# Handy_sense_v_1_0_1.net
KiCad netlist of a schematic drawn in EAGLE
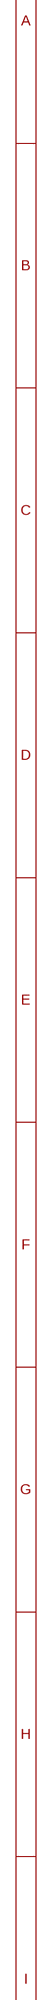
[diagram p0: schematic, sheet 1, part 1 of 2]
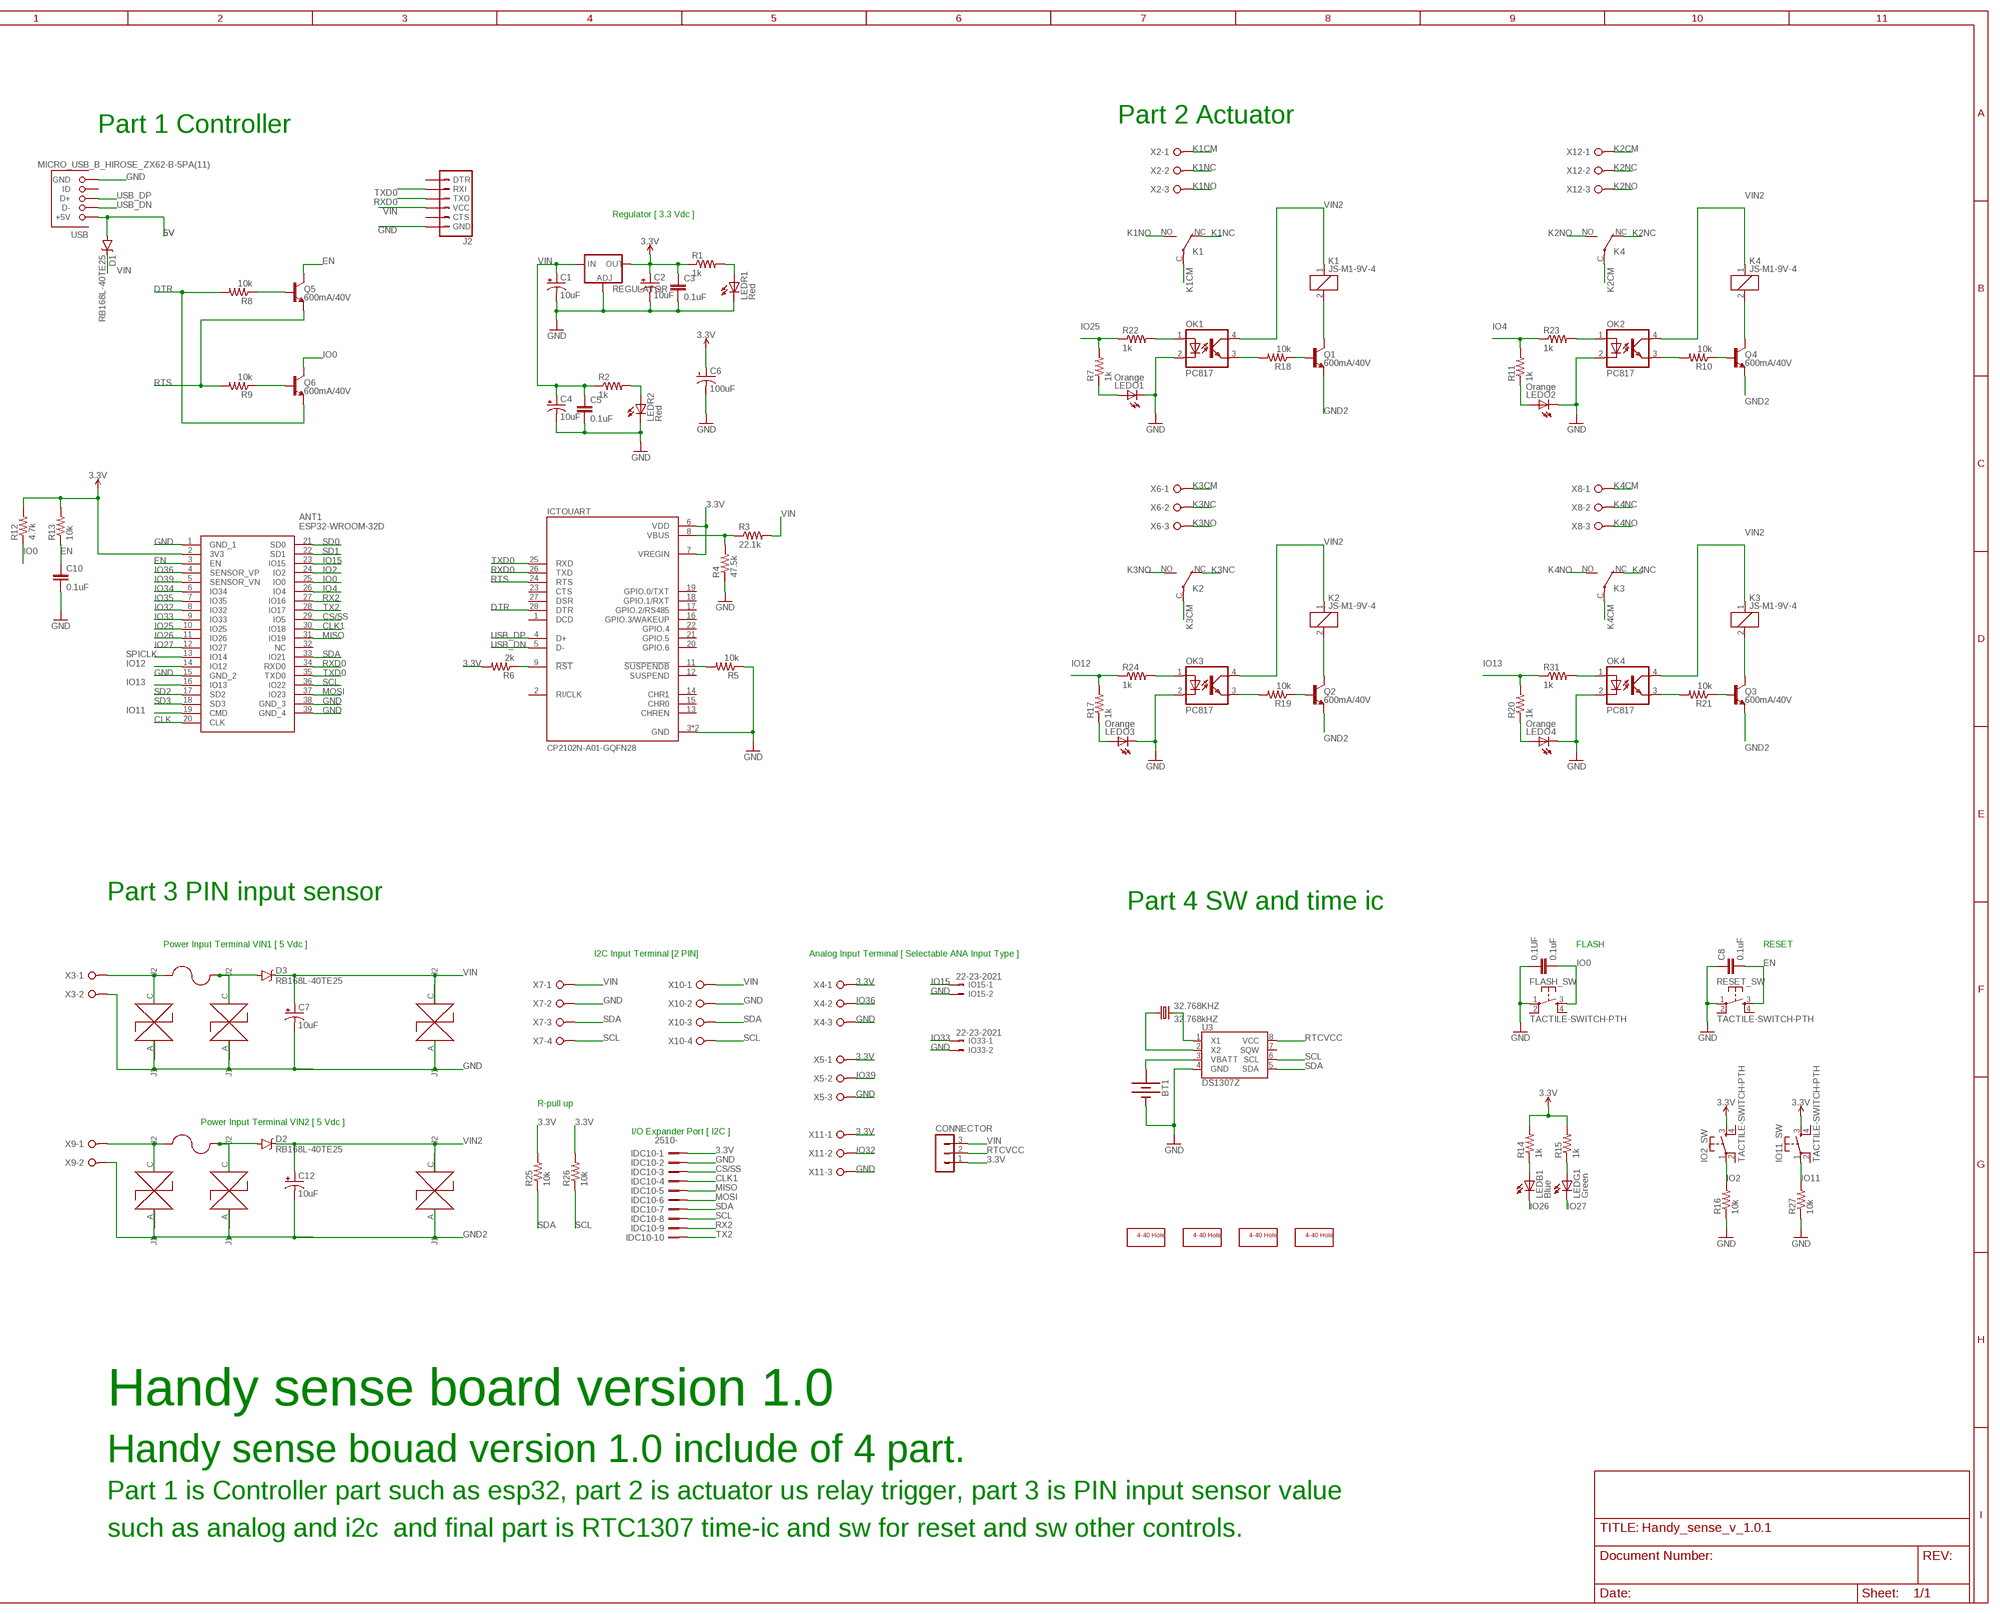
[diagram p1: schematic, sheet 1, part 2 of 2]

(export (version "E")
  (design (tool "Eeschema 10.0.6"))
  (components
    (comp (ref "0.1UF")
      (value "0.1uF")
      (footprint "eagle-import:0805")
      (libsource (lib "eagle-import") (part "CAP0805"))
    )
    (comp (ref "32.768KHZ")
      (value "32.768kHZ")
      (footprint "eagle-import:TC26H")
      (libsource (lib "eagle-import") (part "CRYSTALTC26H"))
    )
    (comp (ref "ANT1")
      (value "ESP32-WROOM-32D")
      (footprint "eagle-import:ESP32WROOM32D")
      (fields (field (name "MOUSER_PART_NUMBER") "356-ESP32WROOM-32D"))
      (libsource (lib "eagle-import") (part "ESP32-WROOM-32D"))
    )
    (comp (ref "BT1")
      (value "BATTERY-20MM_PTH_KIT")
      (footprint "eagle-import:BATTCOM_20MM_PTH_KIT")
      (libsource (lib "eagle-import") (part "BATTERY-20MM_PTH_KIT"))
    )
    (comp (ref "C1")
      (value "10uF")
      (footprint "eagle-import:EIA3216")
      (libsource (lib "eagle-import") (part "10UF-16V-10%(TANT)"))
    )
    (comp (ref "C2")
      (value "10uF")
      (footprint "eagle-import:EIA3216")
      (libsource (lib "eagle-import") (part "10UF-16V-10%(TANT)"))
    )
    (comp (ref "C3")
      (value "0.1uF")
      (footprint "eagle-import:0805")
      (libsource (lib "eagle-import") (part "CAP0805"))
    )
    (comp (ref "C4")
      (value "10uF")
      (footprint "eagle-import:EIA3216")
      (libsource (lib "eagle-import") (part "10UF-16V-10%(TANT)"))
    )
    (comp (ref "C5")
      (value "0.1uF")
      (footprint "eagle-import:0805")
      (libsource (lib "eagle-import") (part "CAP0805"))
    )
    (comp (ref "C6")
      (value "100uF")
      (footprint "eagle-import:EIA7343")
      (libsource (lib "eagle-import") (part "100UF-POLAR-EIA7343-16V-10%(TANT)"))
    )
    (comp (ref "C7")
      (value "10uF")
      (footprint "eagle-import:EIA3216")
      (libsource (lib "eagle-import") (part "10UF-16V-10%(TANT)"))
    )
    (comp (ref "C8")
      (value "0.1uF")
      (footprint "eagle-import:0805")
      (libsource (lib "eagle-import") (part "CAP0805"))
    )
    (comp (ref "C10")
      (value "0.1uF")
      (footprint "eagle-import:0805")
      (libsource (lib "eagle-import") (part "CAP0805"))
    )
    (comp (ref "C12")
      (value "10uF")
      (footprint "eagle-import:EIA3216")
      (libsource (lib "eagle-import") (part "10UF-16V-10%(TANT)"))
    )
    (comp (ref "CONNECTOR")
      (value "MA03-1")
      (footprint "eagle-import:MA03-1")
      (libsource (lib "eagle-import") (part "MA03-1"))
    )
    (comp (ref "D1")
      (value "RB168L-40TE25")
      (footprint "eagle-import:SMA-DIODE")
      (libsource (lib "eagle-import") (part "DIODE-SCHOTTKY-MBRA140"))
    )
    (comp (ref "D2")
      (value "RB168L-40TE25")
      (footprint "eagle-import:SMA-DIODE")
      (libsource (lib "eagle-import") (part "DIODE-SCHOTTKY-MBRA140"))
    )
    (comp (ref "D3")
      (value "RB168L-40TE25")
      (footprint "eagle-import:SMA-DIODE")
      (libsource (lib "eagle-import") (part "DIODE-SCHOTTKY-MBRA140"))
    )
    (comp (ref "FLASH_SW")
      (value "TACTILE-SWITCH-PTH")
      (footprint "eagle-import:TAC-SWITCH-PTH")
      (libsource (lib "eagle-import") (part "TACTILE-SWITCH-PTH"))
    )
    (comp (ref "HOLE0")
      (value "SCREW_HOLE_4-40")
      (footprint "eagle-import:SCREW_HOLE_4-40")
      (libsource (lib "eagle-import") (part "SCREW_HOLE_4-40"))
    )
    (comp (ref "HOLE1")
      (value "SCREW_HOLE_4-40")
      (footprint "eagle-import:SCREW_HOLE_4-40")
      (libsource (lib "eagle-import") (part "SCREW_HOLE_4-40"))
    )
    (comp (ref "HOLE2")
      (value "SCREW_HOLE_4-40")
      (footprint "eagle-import:SCREW_HOLE_4-40")
      (libsource (lib "eagle-import") (part "SCREW_HOLE_4-40"))
    )
    (comp (ref "HOLE3")
      (value "SCREW_HOLE_4-40")
      (footprint "eagle-import:SCREW_HOLE_4-40")
      (libsource (lib "eagle-import") (part "SCREW_HOLE_4-40"))
    )
    (comp (ref "ICTOUART")
      (value "CP2102N-A01-GQFN28")
      (footprint "eagle-import:QFN50P500X500X80-29N")
      (fields (field (name "MF") "Silicon Labs"))
      (libsource (lib "eagle-import") (part "CP2102N-A01-GQFN28"))
    )
    (comp (ref "IDC10")
      (value "2510-")
      (footprint "eagle-import:PAK100_2500-10")
      (fields (field (name "MF") "3M") (field (name "MPN") "2510-6002UB"))
      (libsource (lib "eagle-import") (part "2510-"))
    )
    (comp (ref "IO2_SW")
      (value "TACTILE-SWITCH-PTH")
      (footprint "eagle-import:TAC-SWITCH-PTH")
      (libsource (lib "eagle-import") (part "TACTILE-SWITCH-PTH"))
    )
    (comp (ref "IO11_SW")
      (value "TACTILE-SWITCH-PTH")
      (footprint "eagle-import:TAC-SWITCH-PTH")
      (libsource (lib "eagle-import") (part "TACTILE-SWITCH-PTH"))
    )
    (comp (ref "IO15")
      (value "22-23-2021")
      (footprint "eagle-import:22-23-2021")
      (fields (field (name "MF") "MOLEX"))
      (libsource (lib "eagle-import") (part "22-23-2021"))
    )
    (comp (ref "IO33")
      (value "22-23-2021")
      (footprint "eagle-import:22-23-2021")
      (fields (field (name "MF") "MOLEX"))
      (libsource (lib "eagle-import") (part "22-23-2021"))
    )
    (comp (ref "J2")
      (value "6_PIN_SERIAL_TARGET_SILK")
      (footprint "eagle-import:1X06")
      (libsource (lib "eagle-import") (part "6_PIN_SERIAL_TARGET_SILK"))
    )
    (comp (ref "J28CA1")
      (value "SMBJ28CA")
      (footprint "eagle-import:DIOM505270X240")
      (libsource (lib "eagle-import") (part "SMBJ28CA"))
    )
    (comp (ref "J28CA2")
      (value "SMBJ28CA")
      (footprint "eagle-import:DIOM505270X240")
      (libsource (lib "eagle-import") (part "SMBJ28CA"))
    )
    (comp (ref "J28CA3")
      (value "SMBJ28CA")
      (footprint "eagle-import:DIOM505270X240")
      (libsource (lib "eagle-import") (part "SMBJ28CA"))
    )
    (comp (ref "J28CA4")
      (value "SMBJ28CA")
      (footprint "eagle-import:DIOM505270X240")
      (libsource (lib "eagle-import") (part "SMBJ28CA"))
    )
    (comp (ref "J28CA5")
      (value "SMBJ28CA")
      (footprint "eagle-import:DIOM505270X240")
      (libsource (lib "eagle-import") (part "SMBJ28CA"))
    )
    (comp (ref "J28CA6")
      (value "SMBJ28CA")
      (footprint "eagle-import:DIOM505270X240")
      (libsource (lib "eagle-import") (part "SMBJ28CA"))
    )
    (comp (ref "K1")
      (value "JS-M1-9V-4")
      (footprint "eagle-import:JS-M")
      (libsource (lib "eagle-import") (part "JS-M1-9V-4"))
    )
    (comp (ref "K2")
      (value "JS-M1-9V-4")
      (footprint "eagle-import:JS-M")
      (libsource (lib "eagle-import") (part "JS-M1-9V-4"))
    )
    (comp (ref "K3")
      (value "JS-M1-9V-4")
      (footprint "eagle-import:JS-M")
      (libsource (lib "eagle-import") (part "JS-M1-9V-4"))
    )
    (comp (ref "K4")
      (value "JS-M1-9V-4")
      (footprint "eagle-import:JS-M")
      (libsource (lib "eagle-import") (part "JS-M1-9V-4"))
    )
    (comp (ref "LEDB1")
      (value "Blue")
      (footprint "eagle-import:CHIPLED_0805")
      (libsource (lib "eagle-import") (part "LEDCHIPLED_0805"))
    )
    (comp (ref "LEDG1")
      (value "Green")
      (footprint "eagle-import:CHIPLED_0805")
      (libsource (lib "eagle-import") (part "LEDCHIPLED_0805"))
    )
    (comp (ref "LEDO1")
      (value "Orange")
      (footprint "eagle-import:CHIPLED_0805")
      (libsource (lib "eagle-import") (part "LEDCHIPLED_0805"))
    )
    (comp (ref "LEDO2")
      (value "Orange")
      (footprint "eagle-import:CHIPLED_0805")
      (libsource (lib "eagle-import") (part "LEDCHIPLED_0805"))
    )
    (comp (ref "LEDO3")
      (value "Orange")
      (footprint "eagle-import:CHIPLED_0805")
      (libsource (lib "eagle-import") (part "LEDCHIPLED_0805"))
    )
    (comp (ref "LEDO4")
      (value "Orange")
      (footprint "eagle-import:CHIPLED_0805")
      (libsource (lib "eagle-import") (part "LEDCHIPLED_0805"))
    )
    (comp (ref "LEDR1")
      (value "Red")
      (footprint "eagle-import:CHIPLED_0805")
      (libsource (lib "eagle-import") (part "LEDCHIPLED_0805"))
    )
    (comp (ref "LEDR2")
      (value "Red")
      (footprint "eagle-import:CHIPLED_0805")
      (libsource (lib "eagle-import") (part "LEDCHIPLED_0805"))
    )
    (comp (ref "OK1")
      (value "PC817")
      (footprint "eagle-import:DIL04")
      (fields (field (name "MPN") "PC817X4J000F"))
      (libsource (lib "eagle-import") (part "PC817"))
    )
    (comp (ref "OK2")
      (value "PC817")
      (footprint "eagle-import:DIL04")
      (fields (field (name "MPN") "PC817X4J000F"))
      (libsource (lib "eagle-import") (part "PC817"))
    )
    (comp (ref "OK3")
      (value "PC817")
      (footprint "eagle-import:DIL04")
      (fields (field (name "MPN") "PC817X4J000F"))
      (libsource (lib "eagle-import") (part "PC817"))
    )
    (comp (ref "OK4")
      (value "PC817")
      (footprint "eagle-import:DIL04")
      (fields (field (name "MPN") "PC817X4J000F"))
      (libsource (lib "eagle-import") (part "PC817"))
    )
    (comp (ref "Q1")
      (value "600mA/40V")
      (footprint "eagle-import:SOT23-3")
      (libsource (lib "eagle-import") (part "TRANS_NPN-MMBT2222AL"))
    )
    (comp (ref "Q2")
      (value "600mA/40V")
      (footprint "eagle-import:SOT23-3")
      (libsource (lib "eagle-import") (part "TRANS_NPN-MMBT2222AL"))
    )
    (comp (ref "Q3")
      (value "600mA/40V")
      (footprint "eagle-import:SOT23-3")
      (libsource (lib "eagle-import") (part "TRANS_NPN-MMBT2222AL"))
    )
    (comp (ref "Q4")
      (value "600mA/40V")
      (footprint "eagle-import:SOT23-3")
      (libsource (lib "eagle-import") (part "TRANS_NPN-MMBT2222AL"))
    )
    (comp (ref "Q5")
      (value "600mA/40V")
      (footprint "eagle-import:SOT23-3")
      (libsource (lib "eagle-import") (part "TRANS_NPN-MMBT2222AL"))
    )
    (comp (ref "Q6")
      (value "600mA/40V")
      (footprint "eagle-import:SOT23-3")
      (libsource (lib "eagle-import") (part "TRANS_NPN-MMBT2222AL"))
    )
    (comp (ref "R1")
      (value "1k")
      (footprint "eagle-import:R0805")
      (libsource (lib "eagle-import") (part "R-US_R0805"))
    )
    (comp (ref "R2")
      (value "1k")
      (footprint "eagle-import:R0805")
      (libsource (lib "eagle-import") (part "R-US_R0805"))
    )
    (comp (ref "R3")
      (value "22.1k")
      (footprint "eagle-import:R0805")
      (libsource (lib "eagle-import") (part "R-US_R0805"))
    )
    (comp (ref "R4")
      (value "47.5k")
      (footprint "eagle-import:R0805")
      (libsource (lib "eagle-import") (part "R-US_R0805"))
    )
    (comp (ref "R5")
      (value "10k")
      (footprint "eagle-import:R0805")
      (libsource (lib "eagle-import") (part "R-US_R0805"))
    )
    (comp (ref "R6")
      (value "2k")
      (footprint "eagle-import:R0805")
      (libsource (lib "eagle-import") (part "R-US_R0805"))
    )
    (comp (ref "R7")
      (value "1k")
      (footprint "eagle-import:R0805")
      (libsource (lib "eagle-import") (part "R-US_R0805"))
    )
    (comp (ref "R8")
      (value "10k")
      (footprint "eagle-import:R0805")
      (libsource (lib "eagle-import") (part "R-US_R0805"))
    )
    (comp (ref "R9")
      (value "10k")
      (footprint "eagle-import:R0805")
      (libsource (lib "eagle-import") (part "R-US_R0805"))
    )
    (comp (ref "R10")
      (value "10k")
      (footprint "eagle-import:R0805")
      (libsource (lib "eagle-import") (part "R-US_R0805"))
    )
    (comp (ref "R11")
      (value "1k")
      (footprint "eagle-import:R0805")
      (libsource (lib "eagle-import") (part "R-US_R0805"))
    )
    (comp (ref "R12")
      (value "4.7k")
      (footprint "eagle-import:R0805")
      (libsource (lib "eagle-import") (part "R-US_R0805"))
    )
    (comp (ref "R13")
      (value "10k")
      (footprint "eagle-import:R0805")
      (libsource (lib "eagle-import") (part "R-US_R0805"))
    )
    (comp (ref "R14")
      (value "1k")
      (footprint "eagle-import:R0805")
      (libsource (lib "eagle-import") (part "R-US_R0805"))
    )
    (comp (ref "R15")
      (value "1k")
      (footprint "eagle-import:R0805")
      (libsource (lib "eagle-import") (part "R-US_R0805"))
    )
    (comp (ref "R16")
      (value "10k")
      (footprint "eagle-import:R0805")
      (libsource (lib "eagle-import") (part "R-US_R0805"))
    )
    (comp (ref "R17")
      (value "1k")
      (footprint "eagle-import:R0805")
      (libsource (lib "eagle-import") (part "R-US_R0805"))
    )
    (comp (ref "R18")
      (value "10k")
      (footprint "eagle-import:R0805")
      (libsource (lib "eagle-import") (part "R-US_R0805"))
    )
    (comp (ref "R19")
      (value "10k")
      (footprint "eagle-import:R0805")
      (libsource (lib "eagle-import") (part "R-US_R0805"))
    )
    (comp (ref "R20")
      (value "1k")
      (footprint "eagle-import:R0805")
      (libsource (lib "eagle-import") (part "R-US_R0805"))
    )
    (comp (ref "R21")
      (value "10k")
      (footprint "eagle-import:R0805")
      (libsource (lib "eagle-import") (part "R-US_R0805"))
    )
    (comp (ref "R22")
      (value "1k")
      (footprint "eagle-import:R0805")
      (libsource (lib "eagle-import") (part "R-US_R0805"))
    )
    (comp (ref "R23")
      (value "1k")
      (footprint "eagle-import:R0805")
      (libsource (lib "eagle-import") (part "R-US_R0805"))
    )
    (comp (ref "R24")
      (value "1k")
      (footprint "eagle-import:R0805")
      (libsource (lib "eagle-import") (part "R-US_R0805"))
    )
    (comp (ref "R25")
      (value "10k")
      (footprint "eagle-import:R0805")
      (libsource (lib "eagle-import") (part "R-US_R0805"))
    )
    (comp (ref "R26")
      (value "10k")
      (footprint "eagle-import:R0805")
      (libsource (lib "eagle-import") (part "R-US_R0805"))
    )
    (comp (ref "R27")
      (value "10k")
      (footprint "eagle-import:R0805")
      (libsource (lib "eagle-import") (part "R-US_R0805"))
    )
    (comp (ref "R31")
      (value "1k")
      (footprint "eagle-import:R0805")
      (libsource (lib "eagle-import") (part "R-US_R0805"))
    )
    (comp (ref "REGULATOR")
      (value "V_REG_LM1117SOT223")
      (footprint "eagle-import:SOT223")
      (libsource (lib "eagle-import") (part "V_REG_LM1117SOT223"))
    )
    (comp (ref "RESET_SW")
      (value "TACTILE-SWITCH-PTH")
      (footprint "eagle-import:TAC-SWITCH-PTH")
      (libsource (lib "eagle-import") (part "TACTILE-SWITCH-PTH"))
    )
    (comp (ref "U$1")
      (value "MSMFF2602")
      (footprint "eagle-import:FUSE_MF-MSMF260-2")
      (libsource (lib "eagle-import") (part "MSMFF2602"))
    )
    (comp (ref "U$2")
      (value "MSMFF2602")
      (footprint "eagle-import:FUSE_MF-MSMF260-2")
      (libsource (lib "eagle-import") (part "MSMFF2602"))
    )
    (comp (ref "U3")
      (value "DS1307Z")
      (footprint "eagle-import:SO08-0.15")
      (libsource (lib "eagle-import") (part "DS1307Z"))
    )
    (comp (ref "USB")
      (value "MICRO_USB_B_HIROSE_ZX62-B-5PA(11)")
      (footprint "eagle-import:USB_MICRO_B-HIROSE-ZX62-B-5PA(11)")
      (libsource (lib "eagle-import") (part "MICRO_USB_B_HIROSE_ZX62-B-5PA(11)"))
    )
    (comp (ref "X2")
      (value "W237-03P")
      (footprint "eagle-import:W237-133")
      (libsource (lib "eagle-import") (part "W237-03P"))
    )
    (comp (ref "X3")
      (value "W237-02P")
      (footprint "eagle-import:W237-132")
      (libsource (lib "eagle-import") (part "W237-02P"))
    )
    (comp (ref "X4")
      (value "W237-03P")
      (footprint "eagle-import:W237-133")
      (libsource (lib "eagle-import") (part "W237-03P"))
    )
    (comp (ref "X5")
      (value "W237-03P")
      (footprint "eagle-import:W237-133")
      (libsource (lib "eagle-import") (part "W237-03P"))
    )
    (comp (ref "X6")
      (value "W237-03P")
      (footprint "eagle-import:W237-133")
      (libsource (lib "eagle-import") (part "W237-03P"))
    )
    (comp (ref "X7")
      (value "W237-04P")
      (footprint "eagle-import:W237-4P")
      (libsource (lib "eagle-import") (part "W237-04P"))
    )
    (comp (ref "X8")
      (value "W237-03P")
      (footprint "eagle-import:W237-133")
      (libsource (lib "eagle-import") (part "W237-03P"))
    )
    (comp (ref "X9")
      (value "W237-02P")
      (footprint "eagle-import:W237-132")
      (libsource (lib "eagle-import") (part "W237-02P"))
    )
    (comp (ref "X10")
      (value "W237-04P")
      (footprint "eagle-import:W237-4P")
      (libsource (lib "eagle-import") (part "W237-04P"))
    )
    (comp (ref "X11")
      (value "W237-03P")
      (footprint "eagle-import:W237-133")
      (libsource (lib "eagle-import") (part "W237-03P"))
    )
    (comp (ref "X12")
      (value "W237-03P")
      (footprint "eagle-import:W237-133")
      (libsource (lib "eagle-import") (part "W237-03P"))
    )
  )
  (nets
    (net (code "1") (name "/5V") (class "Default")
      (node (ref "D1") (pin "A") (pinfunction "A_A") (pintype "passive"))
      (node (ref "USB") (pin "1") (pinfunction "+5V_1") (pintype "bidirectional"))
    )
    (net (code "2") (name "/CLK") (class "Default")
      (node (ref "ANT1") (pin "20") (pinfunction "CLK_20") (pintype "bidirectional"))
    )
    (net (code "3") (name "/CLK1") (class "Default")
      (node (ref "ANT1") (pin "30") (pinfunction "IO18_30") (pintype "bidirectional"))
      (node (ref "IDC10") (pin "4") (pinfunction "KL_4") (pintype "passive"))
    )
    (net (code "4") (name "/CS{slash}SS") (class "Default")
      (node (ref "ANT1") (pin "29") (pinfunction "IO5_29") (pintype "bidirectional"))
      (node (ref "IDC10") (pin "3") (pinfunction "KL_3") (pintype "passive"))
    )
    (net (code "5") (name "/DTR") (class "Default")
      (node (ref "ICTOUART") (pin "28") (pinfunction "DTR_28") (pintype "output"))
      (node (ref "Q6") (pin "2") (pinfunction "E_2") (pintype "passive"))
      (node (ref "R8") (pin "2") (pinfunction "2_2") (pintype "passive"))
    )
    (net (code "6") (name "/EN") (class "Default")
      (node (ref "ANT1") (pin "3") (pinfunction "EN_3") (pintype "bidirectional"))
      (node (ref "C10") (pin "1") (pinfunction "1_1") (pintype "passive"))
      (node (ref "C8") (pin "2") (pinfunction "2_2") (pintype "passive"))
      (node (ref "Q5") (pin "3") (pinfunction "C_3") (pintype "passive"))
      (node (ref "R13") (pin "1") (pinfunction "1_1") (pintype "passive"))
      (node (ref "RESET_SW") (pin "3") (pinfunction "3_3") (pintype "passive"))
    )
    (net (code "7") (name "/GND2") (class "Default")
      (node (ref "C12") (pin "C") (pinfunction "-_C") (pintype "passive"))
      (node (ref "J28CA4") (pin "A") (pinfunction "J1_A") (pintype "bidirectional"))
      (node (ref "J28CA5") (pin "A") (pinfunction "J1_A") (pintype "bidirectional"))
      (node (ref "J28CA6") (pin "A") (pinfunction "J1_A") (pintype "bidirectional"))
      (node (ref "Q1") (pin "2") (pinfunction "E_2") (pintype "passive"))
      (node (ref "Q2") (pin "2") (pinfunction "E_2") (pintype "passive"))
      (node (ref "Q3") (pin "2") (pinfunction "E_2") (pintype "passive"))
      (node (ref "Q4") (pin "2") (pinfunction "E_2") (pintype "passive"))
      (node (ref "X9") (pin "2") (pinfunction "KL_2") (pintype "passive"))
    )
    (net (code "8") (name "/IO0") (class "Default")
      (node (ref "0.1UF") (pin "2") (pinfunction "2_2") (pintype "passive"))
      (node (ref "ANT1") (pin "25") (pinfunction "IO0_25") (pintype "bidirectional"))
      (node (ref "FLASH_SW") (pin "3") (pinfunction "3_3") (pintype "passive"))
      (node (ref "Q6") (pin "3") (pinfunction "C_3") (pintype "passive"))
      (node (ref "R12") (pin "1") (pinfunction "1_1") (pintype "passive"))
    )
    (net (code "9") (name "/IO2") (class "Default")
      (node (ref "ANT1") (pin "24") (pinfunction "IO2_24") (pintype "bidirectional"))
      (node (ref "IO2_SW") (pin "1") (pinfunction "1_1") (pintype "passive"))
      (node (ref "R16") (pin "2") (pinfunction "2_2") (pintype "passive"))
    )
    (net (code "10") (name "/IO4") (class "Default")
      (node (ref "ANT1") (pin "26") (pinfunction "IO4_26") (pintype "bidirectional"))
      (node (ref "R11") (pin "2") (pinfunction "2_2") (pintype "passive"))
      (node (ref "R23") (pin "1") (pinfunction "1_1") (pintype "passive"))
    )
    (net (code "11") (name "/IO11") (class "Default")
      (node (ref "ANT1") (pin "19") (pinfunction "CMD_19") (pintype "bidirectional"))
      (node (ref "IO11_SW") (pin "1") (pinfunction "1_1") (pintype "passive"))
      (node (ref "R27") (pin "2") (pinfunction "2_2") (pintype "passive"))
    )
    (net (code "12") (name "/IO12") (class "Default")
      (node (ref "ANT1") (pin "14") (pinfunction "IO12_14") (pintype "bidirectional"))
      (node (ref "R17") (pin "2") (pinfunction "2_2") (pintype "passive"))
      (node (ref "R24") (pin "1") (pinfunction "1_1") (pintype "passive"))
    )
    (net (code "13") (name "/IO13") (class "Default")
      (node (ref "ANT1") (pin "16") (pinfunction "IO13_16") (pintype "bidirectional"))
      (node (ref "R20") (pin "2") (pinfunction "2_2") (pintype "passive"))
      (node (ref "R31") (pin "1") (pinfunction "1_1") (pintype "passive"))
    )
    (net (code "14") (name "/IO15") (class "Default")
      (node (ref "ANT1") (pin "23") (pinfunction "IO15_23") (pintype "bidirectional"))
      (node (ref "IO15") (pin "1") (pinfunction "S_1") (pintype "passive"))
    )
    (net (code "15") (name "/IO25") (class "Default")
      (node (ref "ANT1") (pin "10") (pinfunction "IO25_10") (pintype "bidirectional"))
      (node (ref "R22") (pin "1") (pinfunction "1_1") (pintype "passive"))
      (node (ref "R7") (pin "2") (pinfunction "2_2") (pintype "passive"))
    )
    (net (code "16") (name "/IO26") (class "Default")
      (node (ref "ANT1") (pin "11") (pinfunction "IO26_11") (pintype "bidirectional"))
      (node (ref "LEDB1") (pin "C") (pinfunction "C_C") (pintype "passive"))
    )
    (net (code "17") (name "/IO27") (class "Default")
      (node (ref "ANT1") (pin "12") (pinfunction "IO27_12") (pintype "bidirectional"))
      (node (ref "LEDG1") (pin "C") (pinfunction "C_C") (pintype "passive"))
    )
    (net (code "18") (name "/IO32") (class "Default")
      (node (ref "ANT1") (pin "8") (pinfunction "IO32_8") (pintype "bidirectional"))
      (node (ref "X11") (pin "2") (pinfunction "KL_2") (pintype "passive"))
    )
    (net (code "19") (name "/IO33") (class "Default")
      (node (ref "ANT1") (pin "9") (pinfunction "IO33_9") (pintype "bidirectional"))
      (node (ref "IO33") (pin "1") (pinfunction "S_1") (pintype "passive"))
    )
    (net (code "20") (name "/IO34") (class "Default")
      (node (ref "ANT1") (pin "6") (pinfunction "IO34_6") (pintype "bidirectional"))
    )
    (net (code "21") (name "/IO35") (class "Default")
      (node (ref "ANT1") (pin "7") (pinfunction "IO35_7") (pintype "bidirectional"))
    )
    (net (code "22") (name "/IO36") (class "Default")
      (node (ref "ANT1") (pin "4") (pinfunction "SENSOR_VP_4") (pintype "bidirectional"))
      (node (ref "X4") (pin "2") (pinfunction "KL_2") (pintype "passive"))
    )
    (net (code "23") (name "/IO39") (class "Default")
      (node (ref "ANT1") (pin "5") (pinfunction "SENSOR_VN_5") (pintype "bidirectional"))
      (node (ref "X5") (pin "2") (pinfunction "KL_2") (pintype "passive"))
    )
    (net (code "24") (name "/K1CM") (class "Default")
      (node (ref "K1") (pin "C") (pinfunction "P_C") (pintype "passive"))
      (node (ref "X2") (pin "1") (pinfunction "KL_1") (pintype "passive"))
    )
    (net (code "25") (name "/K1NC") (class "Default")
      (node (ref "K1") (pin "NC") (pinfunction "O_NC") (pintype "passive"))
      (node (ref "X2") (pin "2") (pinfunction "KL_2") (pintype "passive"))
    )
    (net (code "26") (name "/K1NO") (class "Default")
      (node (ref "K1") (pin "NO") (pinfunction "S_NO") (pintype "passive"))
      (node (ref "X2") (pin "3") (pinfunction "KL_3") (pintype "passive"))
    )
    (net (code "27") (name "/K2CM") (class "Default")
      (node (ref "K4") (pin "C") (pinfunction "P_C") (pintype "passive"))
      (node (ref "X12") (pin "1") (pinfunction "KL_1") (pintype "passive"))
    )
    (net (code "28") (name "/K2NC") (class "Default")
      (node (ref "K4") (pin "NC") (pinfunction "O_NC") (pintype "passive"))
      (node (ref "X12") (pin "2") (pinfunction "KL_2") (pintype "passive"))
    )
    (net (code "29") (name "/K2NO") (class "Default")
      (node (ref "K4") (pin "NO") (pinfunction "S_NO") (pintype "passive"))
      (node (ref "X12") (pin "3") (pinfunction "KL_3") (pintype "passive"))
    )
    (net (code "30") (name "/K3CM") (class "Default")
      (node (ref "K2") (pin "C") (pinfunction "P_C") (pintype "passive"))
      (node (ref "X6") (pin "1") (pinfunction "KL_1") (pintype "passive"))
    )
    (net (code "31") (name "/K3NC") (class "Default")
      (node (ref "K2") (pin "NC") (pinfunction "O_NC") (pintype "passive"))
      (node (ref "X6") (pin "2") (pinfunction "KL_2") (pintype "passive"))
    )
    (net (code "32") (name "/K3NO") (class "Default")
      (node (ref "K2") (pin "NO") (pinfunction "S_NO") (pintype "passive"))
      (node (ref "X6") (pin "3") (pinfunction "KL_3") (pintype "passive"))
    )
    (net (code "33") (name "/K4CM") (class "Default")
      (node (ref "K3") (pin "C") (pinfunction "P_C") (pintype "passive"))
      (node (ref "X8") (pin "1") (pinfunction "KL_1") (pintype "passive"))
    )
    (net (code "34") (name "/K4NC") (class "Default")
      (node (ref "K3") (pin "NC") (pinfunction "O_NC") (pintype "passive"))
      (node (ref "X8") (pin "2") (pinfunction "KL_2") (pintype "passive"))
    )
    (net (code "35") (name "/K4NO") (class "Default")
      (node (ref "K3") (pin "NO") (pinfunction "S_NO") (pintype "passive"))
      (node (ref "X8") (pin "3") (pinfunction "KL_3") (pintype "passive"))
    )
    (net (code "36") (name "/MISO") (class "Default")
      (node (ref "ANT1") (pin "31") (pinfunction "IO19_31") (pintype "bidirectional"))
      (node (ref "IDC10") (pin "5") (pinfunction "KL_5") (pintype "passive"))
    )
    (net (code "37") (name "/MOSI") (class "Default")
      (node (ref "ANT1") (pin "37") (pinfunction "IO23_37") (pintype "bidirectional"))
      (node (ref "IDC10") (pin "6") (pinfunction "KL_6") (pintype "passive"))
    )
    (net (code "38") (name "/RTCVCC") (class "Default")
      (node (ref "CONNECTOR") (pin "2") (pinfunction "2_2") (pintype "passive"))
      (node (ref "U3") (pin "8") (pinfunction "VCC_8") (pintype "bidirectional"))
    )
    (net (code "39") (name "/RTS") (class "Default")
      (node (ref "ICTOUART") (pin "24") (pinfunction "RTS_24") (pintype "output"))
      (node (ref "Q5") (pin "2") (pinfunction "E_2") (pintype "passive"))
      (node (ref "R9") (pin "2") (pinfunction "2_2") (pintype "passive"))
    )
    (net (code "40") (name "/RX2") (class "Default")
      (node (ref "ANT1") (pin "27") (pinfunction "IO16_27") (pintype "bidirectional"))
      (node (ref "IDC10") (pin "9") (pinfunction "KL_9") (pintype "passive"))
    )
    (net (code "41") (name "/RXD0") (class "Default")
      (node (ref "ANT1") (pin "34") (pinfunction "RXD0_34") (pintype "bidirectional"))
      (node (ref "ICTOUART") (pin "26") (pinfunction "TXD_26") (pintype "output"))
      (node (ref "J2") (pin "3") (pinfunction "TXO_3") (pintype "passive"))
    )
    (net (code "42") (name "/SCL") (class "Default")
      (node (ref "ANT1") (pin "36") (pinfunction "IO22_36") (pintype "bidirectional"))
      (node (ref "IDC10") (pin "8") (pinfunction "KL_8") (pintype "passive"))
      (node (ref "R26") (pin "1") (pinfunction "1_1") (pintype "passive"))
      (node (ref "U3") (pin "6") (pinfunction "SCL_6") (pintype "bidirectional"))
      (node (ref "X10") (pin "4") (pinfunction "KL_4") (pintype "passive"))
      (node (ref "X7") (pin "4") (pinfunction "KL_4") (pintype "passive"))
    )
    (net (code "43") (name "/SD0") (class "Default")
      (node (ref "ANT1") (pin "21") (pinfunction "SD0_21") (pintype "bidirectional"))
    )
    (net (code "44") (name "/SD1") (class "Default")
      (node (ref "ANT1") (pin "22") (pinfunction "SD1_22") (pintype "bidirectional"))
    )
    (net (code "45") (name "/SD2") (class "Default")
      (node (ref "ANT1") (pin "17") (pinfunction "SD2_17") (pintype "bidirectional"))
    )
    (net (code "46") (name "/SD3") (class "Default")
      (node (ref "ANT1") (pin "18") (pinfunction "SD3_18") (pintype "bidirectional"))
    )
    (net (code "47") (name "/SDA") (class "Default")
      (node (ref "ANT1") (pin "33") (pinfunction "IO21_33") (pintype "bidirectional"))
      (node (ref "IDC10") (pin "7") (pinfunction "KL_7") (pintype "passive"))
      (node (ref "R25") (pin "1") (pinfunction "1_1") (pintype "passive"))
      (node (ref "U3") (pin "5") (pinfunction "SDA_5") (pintype "bidirectional"))
      (node (ref "X10") (pin "3") (pinfunction "KL_3") (pintype "passive"))
      (node (ref "X7") (pin "3") (pinfunction "KL_3") (pintype "passive"))
    )
    (net (code "48") (name "/SPICLK") (class "Default")
      (node (ref "ANT1") (pin "13") (pinfunction "IO14_13") (pintype "bidirectional"))
    )
    (net (code "49") (name "/TX2") (class "Default")
      (node (ref "ANT1") (pin "28") (pinfunction "IO17_28") (pintype "bidirectional"))
      (node (ref "IDC10") (pin "10") (pinfunction "KL_10") (pintype "passive"))
    )
    (net (code "50") (name "/TXD0") (class "Default")
      (node (ref "ANT1") (pin "35") (pinfunction "TXD0_35") (pintype "bidirectional"))
      (node (ref "ICTOUART") (pin "25") (pinfunction "RXD_25") (pintype "input"))
      (node (ref "J2") (pin "2") (pinfunction "RXI_2") (pintype "passive"))
    )
    (net (code "51") (name "/USB_DN") (class "Default")
      (node (ref "ICTOUART") (pin "5") (pinfunction "D-_5") (pintype "bidirectional"))
      (node (ref "USB") (pin "2") (pinfunction "D-_2") (pintype "bidirectional"))
    )
    (net (code "52") (name "/USB_DP") (class "Default")
      (node (ref "ICTOUART") (pin "4") (pinfunction "D+_4") (pintype "bidirectional"))
      (node (ref "USB") (pin "3") (pinfunction "D+_3") (pintype "bidirectional"))
    )
    (net (code "53") (name "/VIN") (class "Default")
      (node (ref "C1") (pin "A") (pinfunction "+_A") (pintype "passive"))
      (node (ref "C4") (pin "A") (pinfunction "+_A") (pintype "passive"))
      (node (ref "C5") (pin "1") (pinfunction "1_1") (pintype "passive"))
      (node (ref "C7") (pin "A") (pinfunction "+_A") (pintype "passive"))
      (node (ref "CONNECTOR") (pin "3") (pinfunction "3_3") (pintype "passive"))
      (node (ref "D1") (pin "C") (pinfunction "C_C") (pintype "passive"))
      (node (ref "D3") (pin "C") (pinfunction "C_C") (pintype "passive"))
      (node (ref "J2") (pin "4") (pinfunction "VCC_4") (pintype "passive"))
      (node (ref "J28CA3") (pin "C") (pinfunction "J2_C") (pintype "bidirectional"))
      (node (ref "R2") (pin "1") (pinfunction "1_1") (pintype "passive"))
      (node (ref "R3") (pin "2") (pinfunction "2_2") (pintype "passive"))
      (node (ref "REGULATOR") (pin "3") (pinfunction "IN_3") (pintype "input"))
      (node (ref "X10") (pin "1") (pinfunction "KL_1") (pintype "passive"))
      (node (ref "X7") (pin "1") (pinfunction "KL_1") (pintype "passive"))
    )
    (net (code "54") (name "/VIN2") (class "Default")
      (node (ref "C12") (pin "A") (pinfunction "+_A") (pintype "passive"))
      (node (ref "D2") (pin "C") (pinfunction "C_C") (pintype "passive"))
      (node (ref "J28CA6") (pin "C") (pinfunction "J2_C") (pintype "bidirectional"))
      (node (ref "K1") (pin "1") (pinfunction "1_1") (pintype "passive"))
      (node (ref "K2") (pin "1") (pinfunction "1_1") (pintype "passive"))
      (node (ref "K3") (pin "1") (pinfunction "1_1") (pintype "passive"))
      (node (ref "K4") (pin "1") (pinfunction "1_1") (pintype "passive"))
      (node (ref "OK1") (pin "4") (pinfunction "COL_4") (pintype "passive"))
      (node (ref "OK2") (pin "4") (pinfunction "COL_4") (pintype "passive"))
      (node (ref "OK3") (pin "4") (pinfunction "COL_4") (pintype "passive"))
      (node (ref "OK4") (pin "4") (pinfunction "COL_4") (pintype "passive"))
    )
    (net (code "55") (name "3.3V") (class "Default")
      (node (ref "ANT1") (pin "2") (pinfunction "3V3_2") (pintype "bidirectional"))
      (node (ref "C2") (pin "A") (pinfunction "+_A") (pintype "passive"))
      (node (ref "C3") (pin "1") (pinfunction "1_1") (pintype "passive"))
      (node (ref "C6") (pin "A") (pinfunction "+_A") (pintype "passive"))
      (node (ref "CONNECTOR") (pin "1") (pinfunction "1_1") (pintype "passive"))
      (node (ref "ICTOUART") (pin "6") (pinfunction "VDD_6") (pintype "power_in"))
      (node (ref "ICTOUART") (pin "7") (pinfunction "VREGIN_7") (pintype "power_in"))
      (node (ref "IDC10") (pin "1") (pinfunction "KL_1") (pintype "passive"))
      (node (ref "IO11_SW") (pin "3") (pinfunction "3_3") (pintype "passive"))
      (node (ref "IO2_SW") (pin "3") (pinfunction "3_3") (pintype "passive"))
      (node (ref "R1") (pin "1") (pinfunction "1_1") (pintype "passive"))
      (node (ref "R12") (pin "2") (pinfunction "2_2") (pintype "passive"))
      (node (ref "R13") (pin "2") (pinfunction "2_2") (pintype "passive"))
      (node (ref "R14") (pin "2") (pinfunction "2_2") (pintype "passive"))
      (node (ref "R15") (pin "2") (pinfunction "2_2") (pintype "passive"))
      (node (ref "R25") (pin "2") (pinfunction "2_2") (pintype "passive"))
      (node (ref "R26") (pin "2") (pinfunction "2_2") (pintype "passive"))
      (node (ref "R6") (pin "2") (pinfunction "2_2") (pintype "passive"))
      (node (ref "REGULATOR") (pin "2") (pinfunction "OUT_2") (pintype "output"))
      (node (ref "REGULATOR") (pin "4") (pinfunction "OUT_4") (pintype "output"))
      (node (ref "X11") (pin "1") (pinfunction "KL_1") (pintype "passive"))
      (node (ref "X4") (pin "1") (pinfunction "KL_1") (pintype "passive"))
      (node (ref "X5") (pin "1") (pinfunction "KL_1") (pintype "passive"))
    )
    (net (code "56") (name "GND") (class "Default")
      (node (ref "0.1UF") (pin "1") (pinfunction "1_1") (pintype "passive"))
      (node (ref "ANT1") (pin "1") (pinfunction "GND_1_1") (pintype "bidirectional"))
      (node (ref "ANT1") (pin "15") (pinfunction "GND_2_15") (pintype "bidirectional"))
      (node (ref "ANT1") (pin "38") (pinfunction "GND_3_38") (pintype "bidirectional"))
      (node (ref "ANT1") (pin "39") (pinfunction "GND_4_39") (pintype "bidirectional"))
      (node (ref "BT1") (pin "2") (pinfunction "-_2") (pintype "power_in"))
      (node (ref "C1") (pin "C") (pinfunction "-_C") (pintype "passive"))
      (node (ref "C10") (pin "2") (pinfunction "2_2") (pintype "passive"))
      (node (ref "C2") (pin "C") (pinfunction "-_C") (pintype "passive"))
      (node (ref "C3") (pin "2") (pinfunction "2_2") (pintype "passive"))
      (node (ref "C4") (pin "C") (pinfunction "-_C") (pintype "passive"))
      (node (ref "C5") (pin "2") (pinfunction "2_2") (pintype "passive"))
      (node (ref "C6") (pin "C") (pinfunction "-_C") (pintype "passive"))
      (node (ref "C7") (pin "C") (pinfunction "-_C") (pintype "passive"))
      (node (ref "C8") (pin "1") (pinfunction "1_1") (pintype "passive"))
      (node (ref "FLASH_SW") (pin "1") (pinfunction "1_1") (pintype "passive"))
      (node (ref "ICTOUART") (pin "29") (pinfunction "GND_29") (pintype "power_in"))
      (node (ref "ICTOUART") (pin "3") (pinfunction "GND_3") (pintype "power_in"))
      (node (ref "IDC10") (pin "2") (pinfunction "KL_2") (pintype "passive"))
      (node (ref "IO15") (pin "2") (pinfunction "S_2") (pintype "passive"))
      (node (ref "IO33") (pin "2") (pinfunction "S_2") (pintype "passive"))
      (node (ref "J2") (pin "6") (pinfunction "GND_6") (pintype "passive"))
      (node (ref "J28CA1") (pin "A") (pinfunction "J1_A") (pintype "bidirectional"))
      (node (ref "J28CA2") (pin "A") (pinfunction "J1_A") (pintype "bidirectional"))
      (node (ref "J28CA3") (pin "A") (pinfunction "J1_A") (pintype "bidirectional"))
      (node (ref "LEDO1") (pin "C") (pinfunction "C_C") (pintype "passive"))
      (node (ref "LEDO2") (pin "C") (pinfunction "C_C") (pintype "passive"))
      (node (ref "LEDO3") (pin "C") (pinfunction "C_C") (pintype "passive"))
      (node (ref "LEDO4") (pin "C") (pinfunction "C_C") (pintype "passive"))
      (node (ref "LEDR1") (pin "C") (pinfunction "C_C") (pintype "passive"))
      (node (ref "LEDR2") (pin "C") (pinfunction "C_C") (pintype "passive"))
      (node (ref "OK1") (pin "2") (pinfunction "C_2") (pintype "passive"))
      (node (ref "OK2") (pin "2") (pinfunction "C_2") (pintype "passive"))
      (node (ref "OK3") (pin "2") (pinfunction "C_2") (pintype "passive"))
      (node (ref "OK4") (pin "2") (pinfunction "C_2") (pintype "passive"))
      (node (ref "R16") (pin "1") (pinfunction "1_1") (pintype "passive"))
      (node (ref "R27") (pin "1") (pinfunction "1_1") (pintype "passive"))
      (node (ref "R4") (pin "1") (pinfunction "1_1") (pintype "passive"))
      (node (ref "R5") (pin "1") (pinfunction "1_1") (pintype "passive"))
      (node (ref "REGULATOR") (pin "1") (pinfunction "ADJ_1") (pintype "input"))
      (node (ref "RESET_SW") (pin "1") (pinfunction "1_1") (pintype "passive"))
      (node (ref "U3") (pin "4") (pinfunction "GND_4") (pintype "bidirectional"))
      (node (ref "USB") (pin "5") (pinfunction "GND_5") (pintype "bidirectional"))
      (node (ref "X10") (pin "2") (pinfunction "KL_2") (pintype "passive"))
      (node (ref "X11") (pin "3") (pinfunction "KL_3") (pintype "passive"))
      (node (ref "X3") (pin "2") (pinfunction "KL_2") (pintype "passive"))
      (node (ref "X4") (pin "3") (pinfunction "KL_3") (pintype "passive"))
      (node (ref "X5") (pin "3") (pinfunction "KL_3") (pintype "passive"))
      (node (ref "X7") (pin "2") (pinfunction "KL_2") (pintype "passive"))
    )
    (net (code "57") (name "Net-(BT1-+)") (class "Default")
      (node (ref "BT1") (pin "1") (pinfunction "+_1") (pintype "power_in"))
      (node (ref "U3") (pin "3") (pinfunction "VBATT_3") (pintype "bidirectional"))
    )
    (net (code "58") (name "Net-(ICTOUART-VBUS)") (class "Default")
      (node (ref "ICTOUART") (pin "8") (pinfunction "VBUS_8") (pintype "power_in"))
      (node (ref "R3") (pin "1") (pinfunction "1_1") (pintype "passive"))
      (node (ref "R4") (pin "2") (pinfunction "2_2") (pintype "passive"))
    )
    (net (code "59") (name "Net-(ICTOUART-~{RST})") (class "Default")
      (node (ref "ICTOUART") (pin "9") (pinfunction "~{RST}_9") (pintype "input"))
      (node (ref "R6") (pin "1") (pinfunction "1_1") (pintype "passive"))
    )
    (net (code "60") (name "Net-(ICTOUART-~{SUSPENDB})") (class "Default")
      (node (ref "ICTOUART") (pin "11") (pinfunction "~{SUSPENDB}_11") (pintype "output"))
      (node (ref "R5") (pin "2") (pinfunction "2_2") (pintype "passive"))
    )
    (net (code "61") (name "Net-(J28CA1-J2)") (class "Default")
      (node (ref "J28CA1") (pin "C") (pinfunction "J2_C") (pintype "bidirectional"))
      (node (ref "U$1") (pin "1") (pinfunction "P1_1") (pintype "input"))
      (node (ref "X3") (pin "1") (pinfunction "KL_1") (pintype "passive"))
    )
    (net (code "62") (name "Net-(J28CA2-J2)") (class "Default")
      (node (ref "D3") (pin "A") (pinfunction "A_A") (pintype "passive"))
      (node (ref "J28CA2") (pin "C") (pinfunction "J2_C") (pintype "bidirectional"))
      (node (ref "U$1") (pin "2") (pinfunction "P$2_2") (pintype "output"))
    )
    (net (code "63") (name "Net-(J28CA4-J2)") (class "Default")
      (node (ref "J28CA4") (pin "C") (pinfunction "J2_C") (pintype "bidirectional"))
      (node (ref "U$2") (pin "1") (pinfunction "P1_1") (pintype "input"))
      (node (ref "X9") (pin "1") (pinfunction "KL_1") (pintype "passive"))
    )
    (net (code "64") (name "Net-(J28CA5-J2)") (class "Default")
      (node (ref "D2") (pin "A") (pinfunction "A_A") (pintype "passive"))
      (node (ref "J28CA5") (pin "C") (pinfunction "J2_C") (pintype "bidirectional"))
      (node (ref "U$2") (pin "2") (pinfunction "P$2_2") (pintype "output"))
    )
    (net (code "65") (name "Net-(LEDB1-PadA)") (class "Default")
      (node (ref "LEDB1") (pin "A") (pinfunction "A_A") (pintype "passive"))
      (node (ref "R14") (pin "1") (pinfunction "1_1") (pintype "passive"))
    )
    (net (code "66") (name "Net-(LEDG1-PadA)") (class "Default")
      (node (ref "LEDG1") (pin "A") (pinfunction "A_A") (pintype "passive"))
      (node (ref "R15") (pin "1") (pinfunction "1_1") (pintype "passive"))
    )
    (net (code "67") (name "Net-(LEDO1-PadA)") (class "Default")
      (node (ref "LEDO1") (pin "A") (pinfunction "A_A") (pintype "passive"))
      (node (ref "R7") (pin "1") (pinfunction "1_1") (pintype "passive"))
    )
    (net (code "68") (name "Net-(LEDO2-PadA)") (class "Default")
      (node (ref "LEDO2") (pin "A") (pinfunction "A_A") (pintype "passive"))
      (node (ref "R11") (pin "1") (pinfunction "1_1") (pintype "passive"))
    )
    (net (code "69") (name "Net-(LEDO3-PadA)") (class "Default")
      (node (ref "LEDO3") (pin "A") (pinfunction "A_A") (pintype "passive"))
      (node (ref "R17") (pin "1") (pinfunction "1_1") (pintype "passive"))
    )
    (net (code "70") (name "Net-(LEDO4-PadA)") (class "Default")
      (node (ref "LEDO4") (pin "A") (pinfunction "A_A") (pintype "passive"))
      (node (ref "R20") (pin "1") (pinfunction "1_1") (pintype "passive"))
    )
    (net (code "71") (name "Net-(LEDR1-PadA)") (class "Default")
      (node (ref "LEDR1") (pin "A") (pinfunction "A_A") (pintype "passive"))
      (node (ref "R1") (pin "2") (pinfunction "2_2") (pintype "passive"))
    )
    (net (code "72") (name "Net-(LEDR2-PadA)") (class "Default")
      (node (ref "LEDR2") (pin "A") (pinfunction "A_A") (pintype "passive"))
      (node (ref "R2") (pin "2") (pinfunction "2_2") (pintype "passive"))
    )
    (net (code "73") (name "Net-(OK1-A)") (class "Default")
      (node (ref "OK1") (pin "1") (pinfunction "A_1") (pintype "passive"))
      (node (ref "R22") (pin "2") (pinfunction "2_2") (pintype "passive"))
    )
    (net (code "74") (name "Net-(OK1-EMIT)") (class "Default")
      (node (ref "OK1") (pin "3") (pinfunction "EMIT_3") (pintype "passive"))
      (node (ref "R18") (pin "2") (pinfunction "2_2") (pintype "passive"))
    )
    (net (code "75") (name "Net-(OK2-A)") (class "Default")
      (node (ref "OK2") (pin "1") (pinfunction "A_1") (pintype "passive"))
      (node (ref "R23") (pin "2") (pinfunction "2_2") (pintype "passive"))
    )
    (net (code "76") (name "Net-(OK2-EMIT)") (class "Default")
      (node (ref "OK2") (pin "3") (pinfunction "EMIT_3") (pintype "passive"))
      (node (ref "R10") (pin "2") (pinfunction "2_2") (pintype "passive"))
    )
    (net (code "77") (name "Net-(OK3-A)") (class "Default")
      (node (ref "OK3") (pin "1") (pinfunction "A_1") (pintype "passive"))
      (node (ref "R24") (pin "2") (pinfunction "2_2") (pintype "passive"))
    )
    (net (code "78") (name "Net-(OK3-EMIT)") (class "Default")
      (node (ref "OK3") (pin "3") (pinfunction "EMIT_3") (pintype "passive"))
      (node (ref "R19") (pin "2") (pinfunction "2_2") (pintype "passive"))
    )
    (net (code "79") (name "Net-(OK4-A)") (class "Default")
      (node (ref "OK4") (pin "1") (pinfunction "A_1") (pintype "passive"))
      (node (ref "R31") (pin "2") (pinfunction "2_2") (pintype "passive"))
    )
    (net (code "80") (name "Net-(OK4-EMIT)") (class "Default")
      (node (ref "OK4") (pin "3") (pinfunction "EMIT_3") (pintype "passive"))
      (node (ref "R21") (pin "2") (pinfunction "2_2") (pintype "passive"))
    )
    (net (code "81") (name "Net-(Q1-B)") (class "Default")
      (node (ref "Q1") (pin "1") (pinfunction "B_1") (pintype "passive"))
      (node (ref "R18") (pin "1") (pinfunction "1_1") (pintype "passive"))
    )
    (net (code "82") (name "Net-(Q1-C)") (class "Default")
      (node (ref "K1") (pin "2") (pinfunction "2_2") (pintype "passive"))
      (node (ref "Q1") (pin "3") (pinfunction "C_3") (pintype "passive"))
    )
    (net (code "83") (name "Net-(Q2-B)") (class "Default")
      (node (ref "Q2") (pin "1") (pinfunction "B_1") (pintype "passive"))
      (node (ref "R19") (pin "1") (pinfunction "1_1") (pintype "passive"))
    )
    (net (code "84") (name "Net-(Q2-C)") (class "Default")
      (node (ref "K2") (pin "2") (pinfunction "2_2") (pintype "passive"))
      (node (ref "Q2") (pin "3") (pinfunction "C_3") (pintype "passive"))
    )
    (net (code "85") (name "Net-(Q3-B)") (class "Default")
      (node (ref "Q3") (pin "1") (pinfunction "B_1") (pintype "passive"))
      (node (ref "R21") (pin "1") (pinfunction "1_1") (pintype "passive"))
    )
    (net (code "86") (name "Net-(Q3-C)") (class "Default")
      (node (ref "K3") (pin "2") (pinfunction "2_2") (pintype "passive"))
      (node (ref "Q3") (pin "3") (pinfunction "C_3") (pintype "passive"))
    )
    (net (code "87") (name "Net-(Q4-B)") (class "Default")
      (node (ref "Q4") (pin "1") (pinfunction "B_1") (pintype "passive"))
      (node (ref "R10") (pin "1") (pinfunction "1_1") (pintype "passive"))
    )
    (net (code "88") (name "Net-(Q4-C)") (class "Default")
      (node (ref "K4") (pin "2") (pinfunction "2_2") (pintype "passive"))
      (node (ref "Q4") (pin "3") (pinfunction "C_3") (pintype "passive"))
    )
    (net (code "89") (name "Net-(Q5-B)") (class "Default")
      (node (ref "Q5") (pin "1") (pinfunction "B_1") (pintype "passive"))
      (node (ref "R8") (pin "1") (pinfunction "1_1") (pintype "passive"))
    )
    (net (code "90") (name "Net-(Q6-B)") (class "Default")
      (node (ref "Q6") (pin "1") (pinfunction "B_1") (pintype "passive"))
      (node (ref "R9") (pin "1") (pinfunction "1_1") (pintype "passive"))
    )
    (net (code "91") (name "Net-(U3-X1)") (class "Default")
      (node (ref "32.768KHZ") (pin "2") (pinfunction "2_2") (pintype "passive"))
      (node (ref "U3") (pin "1") (pinfunction "X1_1") (pintype "bidirectional"))
    )
    (net (code "92") (name "Net-(U3-X2)") (class "Default")
      (node (ref "32.768KHZ") (pin "1") (pinfunction "1_1") (pintype "passive"))
      (node (ref "U3") (pin "2") (pinfunction "X2_2") (pintype "bidirectional"))
    )
    (net (code "93") (name "unconnected-(ANT1-NC-Pad32)") (class "Default")
      (node (ref "ANT1") (pin "32") (pinfunction "NC_32") (pintype "no_connect"))
    )
    (net (code "94") (name "unconnected-(FLASH_SW-Pad2)") (class "Default")
      (node (ref "FLASH_SW") (pin "2") (pinfunction "2_2") (pintype "passive"))
    )
    (net (code "95") (name "unconnected-(FLASH_SW-Pad4)") (class "Default")
      (node (ref "FLASH_SW") (pin "4") (pinfunction "4_4") (pintype "passive"))
    )
    (net (code "96") (name "unconnected-(ICTOUART-CHR0-Pad15)") (class "Default")
      (node (ref "ICTOUART") (pin "15") (pinfunction "CHR0_15") (pintype "output"))
    )
    (net (code "97") (name "unconnected-(ICTOUART-CHR1-Pad14)") (class "Default")
      (node (ref "ICTOUART") (pin "14") (pinfunction "CHR1_14") (pintype "output"))
    )
    (net (code "98") (name "unconnected-(ICTOUART-CHREN-Pad13)") (class "Default")
      (node (ref "ICTOUART") (pin "13") (pinfunction "CHREN_13") (pintype "output"))
    )
    (net (code "99") (name "unconnected-(ICTOUART-CTS-Pad23)") (class "Default")
      (node (ref "ICTOUART") (pin "23") (pinfunction "CTS_23") (pintype "input"))
    )
    (net (code "100") (name "unconnected-(ICTOUART-DCD-Pad1)") (class "Default")
      (node (ref "ICTOUART") (pin "1") (pinfunction "DCD_1") (pintype "input"))
    )
    (net (code "101") (name "unconnected-(ICTOUART-DSR-Pad27)") (class "Default")
      (node (ref "ICTOUART") (pin "27") (pinfunction "DSR_27") (pintype "input"))
    )
    (net (code "102") (name "unconnected-(ICTOUART-GPIO.0{slash}TXT-Pad19)") (class "Default")
      (node (ref "ICTOUART") (pin "19") (pinfunction "GPIO.0/TXT_19") (pintype "bidirectional"))
    )
    (net (code "103") (name "unconnected-(ICTOUART-GPIO.1{slash}RXT-Pad18)") (class "Default")
      (node (ref "ICTOUART") (pin "18") (pinfunction "GPIO.1/RXT_18") (pintype "bidirectional"))
    )
    (net (code "104") (name "unconnected-(ICTOUART-GPIO.2{slash}RS485-Pad17)") (class "Default")
      (node (ref "ICTOUART") (pin "17") (pinfunction "GPIO.2/RS485_17") (pintype "bidirectional"))
    )
    (net (code "105") (name "unconnected-(ICTOUART-GPIO.3{slash}WAKEUP-Pad16)") (class "Default")
      (node (ref "ICTOUART") (pin "16") (pinfunction "GPIO.3/WAKEUP_16") (pintype "bidirectional"))
    )
    (net (code "106") (name "unconnected-(ICTOUART-GPIO.4-Pad22)") (class "Default")
      (node (ref "ICTOUART") (pin "22") (pinfunction "GPIO.4_22") (pintype "bidirectional"))
    )
    (net (code "107") (name "unconnected-(ICTOUART-GPIO.5-Pad21)") (class "Default")
      (node (ref "ICTOUART") (pin "21") (pinfunction "GPIO.5_21") (pintype "bidirectional"))
    )
    (net (code "108") (name "unconnected-(ICTOUART-GPIO.6-Pad20)") (class "Default")
      (node (ref "ICTOUART") (pin "20") (pinfunction "GPIO.6_20") (pintype "bidirectional"))
    )
    (net (code "109") (name "unconnected-(ICTOUART-RI{slash}CLK-Pad2)") (class "Default")
      (node (ref "ICTOUART") (pin "2") (pinfunction "RI/CLK_2") (pintype "bidirectional"))
    )
    (net (code "110") (name "unconnected-(ICTOUART-SUSPEND-Pad12)") (class "Default")
      (node (ref "ICTOUART") (pin "12") (pinfunction "SUSPEND_12") (pintype "output"))
    )
    (net (code "111") (name "unconnected-(IO2_SW-Pad2)") (class "Default")
      (node (ref "IO2_SW") (pin "2") (pinfunction "2_2") (pintype "passive"))
    )
    (net (code "112") (name "unconnected-(IO2_SW-Pad4)") (class "Default")
      (node (ref "IO2_SW") (pin "4") (pinfunction "4_4") (pintype "passive"))
    )
    (net (code "113") (name "unconnected-(IO11_SW-Pad2)") (class "Default")
      (node (ref "IO11_SW") (pin "2") (pinfunction "2_2") (pintype "passive"))
    )
    (net (code "114") (name "unconnected-(IO11_SW-Pad4)") (class "Default")
      (node (ref "IO11_SW") (pin "4") (pinfunction "4_4") (pintype "passive"))
    )
    (net (code "115") (name "unconnected-(J2-CTS-Pad5)") (class "Default")
      (node (ref "J2") (pin "5") (pinfunction "CTS_5") (pintype "passive"))
    )
    (net (code "116") (name "unconnected-(J2-DTR-Pad1)") (class "Default")
      (node (ref "J2") (pin "1") (pinfunction "DTR_1") (pintype "passive"))
    )
    (net (code "117") (name "unconnected-(RESET_SW-Pad2)") (class "Default")
      (node (ref "RESET_SW") (pin "2") (pinfunction "2_2") (pintype "passive"))
    )
    (net (code "118") (name "unconnected-(RESET_SW-Pad4)") (class "Default")
      (node (ref "RESET_SW") (pin "4") (pinfunction "4_4") (pintype "passive"))
    )
    (net (code "119") (name "unconnected-(U3-SQW-Pad7)") (class "Default")
      (node (ref "U3") (pin "7") (pinfunction "SQW_7") (pintype "bidirectional"))
    )
    (net (code "120") (name "unconnected-(USB-ID-Pad4)") (class "Default")
      (node (ref "USB") (pin "4") (pinfunction "ID_4") (pintype "bidirectional"))
    )
  )
)
